# STM3205P_DACSPI.net
KiCad netlist of a schematic drawn in Altium Designer
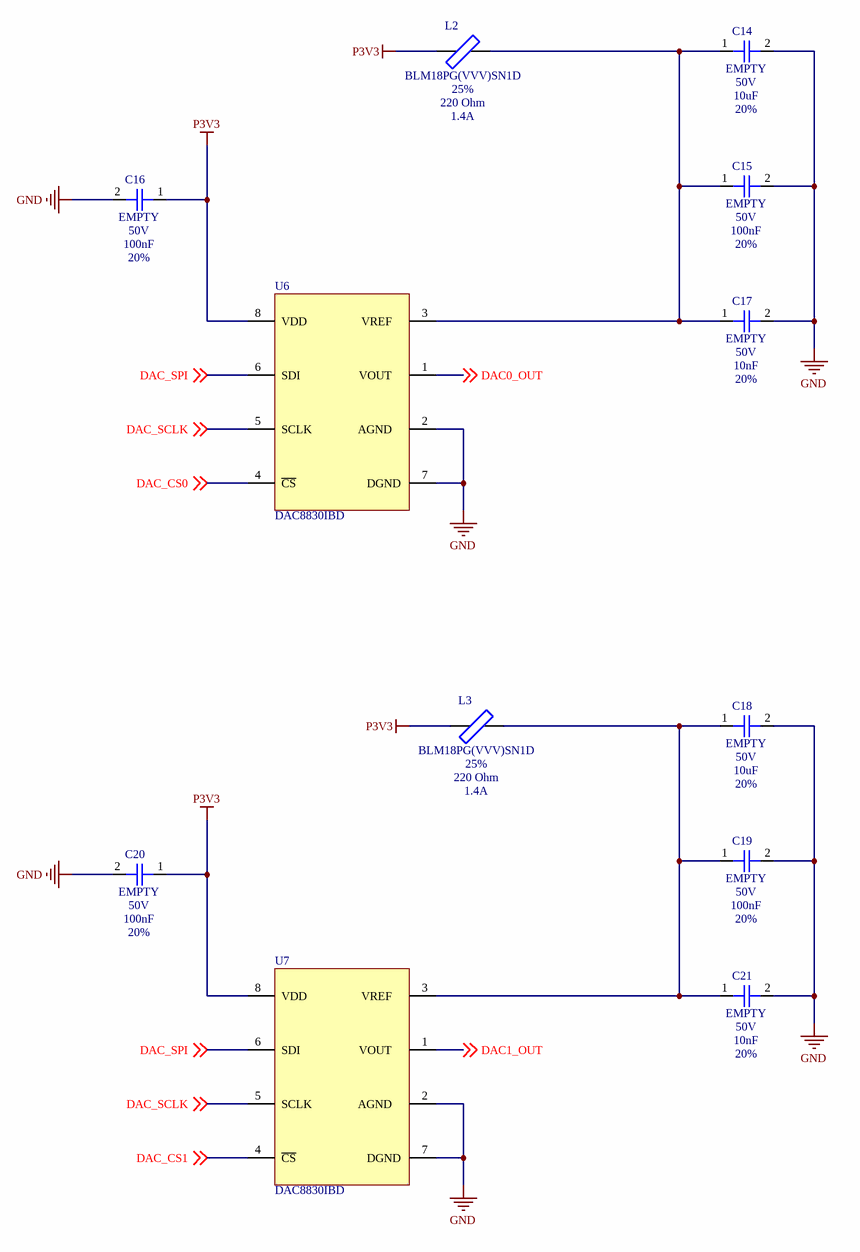
[diagram p0: STM3205P_DACSPI.SchDoc]

(export (version "E")
  (design (tool "Eeschema 10.0.6"))
  (components
    (comp (ref "C14")
      (value "10uF")
      (footprint "CAP0603")
      (description "Surface Mount Multilayer Ceramic Chip Capacitors  for Commercial Applications")
      (fields
        (field (name "PARTNUMBER1") "EMPTY")
        (field (name "VOLTAGE") "50V")
        (field (name "TOLERANCE") "20%")
        (field (name "Comment") "CC0603")
        (field (name "PUBLISHER") "Lucas Moraes")
      )
      (libsource (lib "CeramicCapacitors") (part "CC0603"))
    )
    (comp (ref "C15")
      (value "100nF")
      (footprint "CAP0603")
      (description "Surface Mount Multilayer Ceramic Chip Capacitors  for Commercial Applications")
      (fields
        (field (name "PARTNUMBER1") "EMPTY")
        (field (name "VOLTAGE") "50V")
        (field (name "TOLERANCE") "20%")
        (field (name "Comment") "CC0603")
        (field (name "PUBLISHER") "Lucas Moraes")
      )
      (libsource (lib "CeramicCapacitors") (part "CC0603"))
    )
    (comp (ref "C16")
      (value "100nF")
      (footprint "CAP0603")
      (description "Surface Mount Multilayer Ceramic Chip Capacitors  for Commercial Applications")
      (fields
        (field (name "PARTNUMBER1") "EMPTY")
        (field (name "VOLTAGE") "50V")
        (field (name "TOLERANCE") "20%")
        (field (name "Comment") "CC0603")
        (field (name "PUBLISHER") "Lucas Moraes")
      )
      (libsource (lib "CeramicCapacitors") (part "CC0603"))
    )
    (comp (ref "C17")
      (value "10nF")
      (footprint "CAP0603")
      (description "Surface Mount Multilayer Ceramic Chip Capacitors  for Commercial Applications")
      (fields
        (field (name "PARTNUMBER1") "EMPTY")
        (field (name "VOLTAGE") "50V")
        (field (name "TOLERANCE") "20%")
        (field (name "Comment") "CC0603")
        (field (name "PUBLISHER") "Lucas Moraes")
      )
      (libsource (lib "CeramicCapacitors") (part "CC0603"))
    )
    (comp (ref "C18")
      (value "10uF")
      (footprint "CAP0603")
      (description "Surface Mount Multilayer Ceramic Chip Capacitors  for Commercial Applications")
      (fields
        (field (name "PARTNUMBER1") "EMPTY")
        (field (name "VOLTAGE") "50V")
        (field (name "TOLERANCE") "20%")
        (field (name "Comment") "CC0603")
        (field (name "PUBLISHER") "Lucas Moraes")
      )
      (libsource (lib "CeramicCapacitors") (part "CC0603"))
    )
    (comp (ref "C19")
      (value "100nF")
      (footprint "CAP0603")
      (description "Surface Mount Multilayer Ceramic Chip Capacitors  for Commercial Applications")
      (fields
        (field (name "PARTNUMBER1") "EMPTY")
        (field (name "VOLTAGE") "50V")
        (field (name "TOLERANCE") "20%")
        (field (name "Comment") "CC0603")
        (field (name "PUBLISHER") "Lucas Moraes")
      )
      (libsource (lib "CeramicCapacitors") (part "CC0603"))
    )
    (comp (ref "C20")
      (value "100nF")
      (footprint "CAP0603")
      (description "Surface Mount Multilayer Ceramic Chip Capacitors  for Commercial Applications")
      (fields
        (field (name "PARTNUMBER1") "EMPTY")
        (field (name "VOLTAGE") "50V")
        (field (name "TOLERANCE") "20%")
        (field (name "Comment") "CC0603")
        (field (name "PUBLISHER") "Lucas Moraes")
      )
      (libsource (lib "CeramicCapacitors") (part "CC0603"))
    )
    (comp (ref "C21")
      (value "10nF")
      (footprint "CAP0603")
      (description "Surface Mount Multilayer Ceramic Chip Capacitors  for Commercial Applications")
      (fields
        (field (name "PARTNUMBER1") "EMPTY")
        (field (name "VOLTAGE") "50V")
        (field (name "TOLERANCE") "20%")
        (field (name "Comment") "CC0603")
        (field (name "PUBLISHER") "Lucas Moraes")
      )
      (libsource (lib "CeramicCapacitors") (part "CC0603"))
    )
    (comp (ref "L2")
      (value "220 Ohm")
      (footprint "IND0603")
      (description "Ferrite Beads 0603")
      (fields
        (field (name "PARTNUMBER1") "BLM18PG(VVV)SN1D")
        (field (name "TOLERANCE") "25%")
        (field (name "CURRENT") "1.4A")
        (field (name "Comment") "BLM18")
        (field (name "PUBLISHER") "Lucas Moraes")
      )
      (libsource (lib "Inductor") (part "BLM18"))
    )
    (comp (ref "L3")
      (value "220 Ohm")
      (footprint "IND0603")
      (description "Ferrite Beads 0603")
      (fields
        (field (name "PARTNUMBER1") "BLM18PG(VVV)SN1D")
        (field (name "TOLERANCE") "25%")
        (field (name "CURRENT") "1.4A")
        (field (name "Comment") "BLM18")
        (field (name "PUBLISHER") "Lucas Moraes")
      )
      (libsource (lib "Inductor") (part "BLM18"))
    )
    (comp (ref "U6")
      (value "DAC8830ICD")
      (footprint "SOIC-08-3.9mm")
      (description "DAC Lo-Pwr R-To-R Output 16-Bit Serial Input")
      (fields (field (name "PARTNUMBER1") "DAC8830IBD") (field (name "PUBLISHER") "Lucas Moraes"))
      (libsource (lib "DigitalAnalogConverter") (part "DAC8830ICD"))
    )
    (comp (ref "U7")
      (value "DAC8830ICD")
      (footprint "SOIC-08-3.9mm")
      (description "DAC Lo-Pwr R-To-R Output 16-Bit Serial Input")
      (fields (field (name "PARTNUMBER1") "DAC8830IBD") (field (name "PUBLISHER") "Lucas Moraes"))
      (libsource (lib "DigitalAnalogConverter") (part "DAC8830ICD"))
    )
  )
  (nets
    (net (code "1") (name "DAC0_OUT") (class "Default")
      (node (ref "U6") (pin "1") (pinfunction "VOUT_1") (pintype "passive"))
    )
    (net (code "2") (name "DAC1_OUT") (class "Default")
      (node (ref "U7") (pin "1") (pinfunction "VOUT_1") (pintype "passive"))
    )
    (net (code "3") (name "DAC_CS0") (class "Default")
      (node (ref "U6") (pin "4") (pinfunction "~{CS}_4") (pintype "passive"))
    )
    (net (code "4") (name "DAC_CS1") (class "Default")
      (node (ref "U7") (pin "4") (pinfunction "~{CS}_4") (pintype "passive"))
    )
    (net (code "5") (name "DAC_SCLK") (class "Default")
      (node (ref "U6") (pin "5") (pinfunction "SCLK_5") (pintype "passive"))
      (node (ref "U7") (pin "5") (pinfunction "SCLK_5") (pintype "passive"))
    )
    (net (code "6") (name "DAC_SPI") (class "Default")
      (node (ref "U6") (pin "6") (pinfunction "SDI_6") (pintype "passive"))
      (node (ref "U7") (pin "6") (pinfunction "SDI_6") (pintype "passive"))
    )
    (net (code "7") (name "GND") (class "Default")
      (node (ref "C14") (pin "2") (pinfunction "2_2") (pintype "passive"))
      (node (ref "C15") (pin "2") (pinfunction "2_2") (pintype "passive"))
      (node (ref "C16") (pin "2") (pinfunction "2_2") (pintype "passive"))
      (node (ref "C17") (pin "2") (pinfunction "2_2") (pintype "passive"))
      (node (ref "C18") (pin "2") (pinfunction "2_2") (pintype "passive"))
      (node (ref "C19") (pin "2") (pinfunction "2_2") (pintype "passive"))
      (node (ref "C20") (pin "2") (pinfunction "2_2") (pintype "passive"))
      (node (ref "C21") (pin "2") (pinfunction "2_2") (pintype "passive"))
      (node (ref "U6") (pin "2") (pinfunction "AGND_2") (pintype "power_in"))
      (node (ref "U6") (pin "7") (pinfunction "DGND_7") (pintype "power_in"))
      (node (ref "U7") (pin "2") (pinfunction "AGND_2") (pintype "power_in"))
      (node (ref "U7") (pin "7") (pinfunction "DGND_7") (pintype "power_in"))
    )
    (net (code "8") (name "Net-(U6-VREF)") (class "Default")
      (node (ref "C14") (pin "1") (pinfunction "1_1") (pintype "passive"))
      (node (ref "C15") (pin "1") (pinfunction "1_1") (pintype "passive"))
      (node (ref "C17") (pin "1") (pinfunction "1_1") (pintype "passive"))
      (node (ref "L2") (pin "1") (pinfunction "1_1") (pintype "passive"))
      (node (ref "U6") (pin "3") (pinfunction "VREF_3") (pintype "passive"))
    )
    (net (code "9") (name "Net-(U7-VREF)") (class "Default")
      (node (ref "C18") (pin "1") (pinfunction "1_1") (pintype "passive"))
      (node (ref "C19") (pin "1") (pinfunction "1_1") (pintype "passive"))
      (node (ref "C21") (pin "1") (pinfunction "1_1") (pintype "passive"))
      (node (ref "L3") (pin "1") (pinfunction "1_1") (pintype "passive"))
      (node (ref "U7") (pin "3") (pinfunction "VREF_3") (pintype "passive"))
    )
    (net (code "10") (name "P3V3") (class "Default")
      (node (ref "C16") (pin "1") (pinfunction "1_1") (pintype "passive"))
      (node (ref "C20") (pin "1") (pinfunction "1_1") (pintype "passive"))
      (node (ref "L2") (pin "2") (pinfunction "2_2") (pintype "passive"))
      (node (ref "L3") (pin "2") (pinfunction "2_2") (pintype "passive"))
      (node (ref "U6") (pin "8") (pinfunction "VDD_8") (pintype "power_in"))
      (node (ref "U7") (pin "8") (pinfunction "VDD_8") (pintype "power_in"))
    )
  )
)
